# AAS_touch_board_rev1_1.net
KiCad netlist of a schematic drawn in Altium Designer
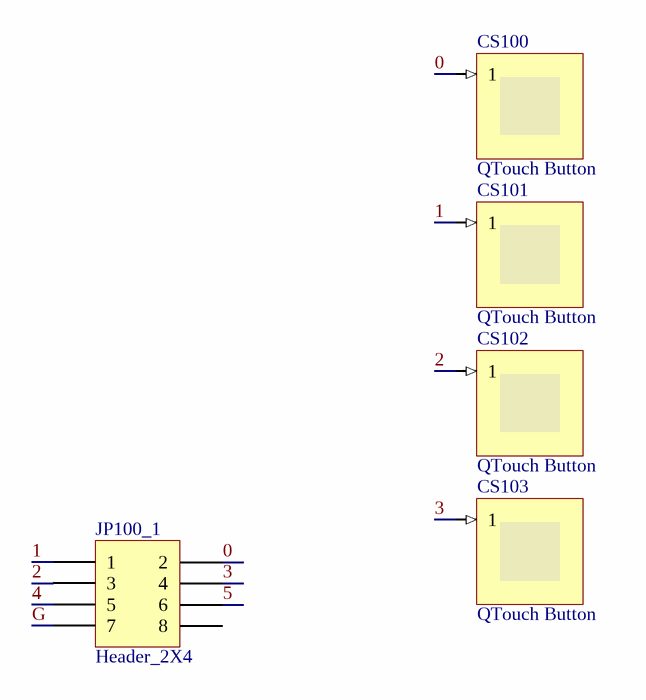
[diagram p0: AAS_touch_board_rev1_1.SchDoc]

(export (version "E")
  (design (tool "Eeschema 10.0.6"))
  (components
    (comp (ref "CS100") (value "QTouch Button") (libsource (lib "Atmel QTouch") (part "QTouchButton")))
    (comp (ref "CS101") (value "QTouch Button") (libsource (lib "Atmel QTouch") (part "QTouchButton")))
    (comp (ref "CS102") (value "QTouch Button") (libsource (lib "Atmel QTouch") (part "QTouchButton")))
    (comp (ref "CS103") (value "QTouch Button") (libsource (lib "Atmel QTouch") (part "QTouchButton")))
    (comp (ref "JP100_1")
      (value "Header_2X4")
      (footprint "HDR2X4")
      (description "Header dual row")
      (libsource (lib "ELEKON") (part "Header2X4"))
    )
  )
  (nets
    (net (code "1") (name "/0") (class "Default")
      (node (ref "CS100") (pin "1") (pinfunction "1_1") (pintype "input"))
      (node (ref "JP100_1") (pin "2") (pinfunction "2_2") (pintype "passive"))
    )
    (net (code "2") (name "/1") (class "Default")
      (node (ref "CS101") (pin "1") (pinfunction "1_1") (pintype "input"))
      (node (ref "JP100_1") (pin "1") (pinfunction "1_1") (pintype "passive"))
    )
    (net (code "3") (name "/2") (class "Default")
      (node (ref "CS102") (pin "1") (pinfunction "1_1") (pintype "input"))
      (node (ref "JP100_1") (pin "3") (pinfunction "3_3") (pintype "passive"))
    )
    (net (code "4") (name "/3") (class "Default")
      (node (ref "CS103") (pin "1") (pinfunction "1_1") (pintype "input"))
      (node (ref "JP100_1") (pin "4") (pinfunction "4_4") (pintype "passive"))
    )
    (net (code "5") (name "/4") (class "Default")
      (node (ref "JP100_1") (pin "5") (pinfunction "5_5") (pintype "passive"))
    )
    (net (code "6") (name "/5") (class "Default")
      (node (ref "JP100_1") (pin "6") (pinfunction "6_6") (pintype "passive"))
    )
    (net (code "7") (name "/G") (class "Default")
      (node (ref "JP100_1") (pin "7") (pinfunction "7_7") (pintype "passive"))
    )
    (net (code "8") (name "unconnected-(JP100_1-Pad8)") (class "Default")
      (node (ref "JP100_1") (pin "8") (pinfunction "8_8") (pintype "passive"))
    )
  )
)
